# Power_circuit.net
KiCad netlist of a schematic drawn in Altium Designer
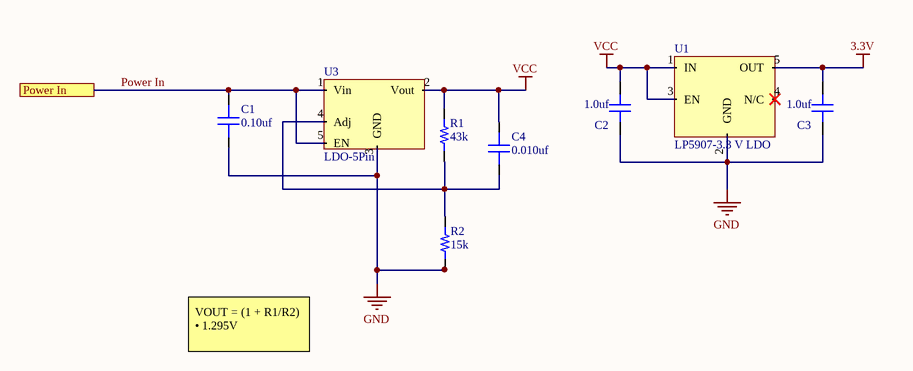
[diagram p0: Power circuit.SchDoc]

(export (version "E")
  (design (tool "Eeschema 10.0.6"))
  (components
    (comp (ref "C1")
      (value "0.10uf")
      (footprint "CAP 0603/1608")
      (fields
        (field (name "Comment") "Capacitor MLCC 0.10uf 16V CAP 0603/1608")
        (field (name "CREATED_BY") "Nick Mah")
      )
      (libsource (lib "Altium-Lib") (part "Capacitor"))
    )
    (comp (ref "C2")
      (value "1.0uf")
      (footprint "CAP 0603/1608")
      (fields
        (field (name "Comment") "Capacitor MLCC 1.0uf 16V CAP 0603/1608")
        (field (name "CREATED_BY") "Nick Mah")
      )
      (libsource (lib "") (part "Capacitor_1"))
    )
    (comp (ref "C3")
      (value "1.0uf")
      (footprint "CAP 0603/1608")
      (fields
        (field (name "Comment") "Capacitor MLCC 1.0uf 16V CAP 0603/1608")
        (field (name "CREATED_BY") "Nick Mah")
      )
      (libsource (lib "") (part "Capacitor_1"))
    )
    (comp (ref "C4")
      (value "0.010uf")
      (footprint "CAP 0603/1608")
      (fields
        (field (name "Comment") "Capacitor MLCC 0.010uf 16V CAP 0603/1608")
        (field (name "CREATED_BY") "Nick Mah")
      )
      (libsource (lib "Altium-Lib") (part "Capacitor"))
    )
    (comp (ref "R1")
      (value "43k")
      (footprint "RES 0603/1608")
      (fields
        (field (name "TOLERANCE") "1%")
        (field (name "POWER") "1/10W")
        (field (name "Comment") "Resistor 43k 0603 1/10W 1%")
        (field (name "CREATED_BY") "Nick Mah")
      )
      (libsource (lib "Altium-Lib") (part "Resistor"))
    )
    (comp (ref "R2")
      (value "15k")
      (footprint "RES 0603/1608")
      (fields
        (field (name "TOLERANCE") "1%")
        (field (name "POWER") "1/10W")
        (field (name "Comment") "Resistor 15k 0603 1/10W 1%")
        (field (name "CREATED_BY") "Nick Mah")
      )
      (libsource (lib "Altium-Lib") (part "Resistor"))
    )
    (comp (ref "U1")
      (value "LP5907-3.3 V LDO")
      (footprint "SOT23-5")
      (fields (field (name "MFRPARTNO") "LP5907MFX-3.3/NOPB"))
      (libsource (lib "Altium-Lib") (part "LP5907-3.3 V LDO"))
    )
    (comp (ref "U3")
      (value "LDO-5Pin")
      (footprint "SOT223-5")
      (fields (field (name "MFRPARTNO") "REG104GA-A"))
      (libsource (lib "Altium-Lib") (part "LDO-5Pin"))
    )
  )
  (nets
    (net (code "1") (name "/Power In") (class "Default")
      (node (ref "C1") (pin "2") (pinfunction "2_2") (pintype "passive"))
      (node (ref "U3") (pin "1") (pinfunction "Vin_1") (pintype "input"))
      (node (ref "U3") (pin "5") (pinfunction "EN_5") (pintype "input"))
    )
    (net (code "2") (name "3.3V") (class "Default")
      (node (ref "C3") (pin "2") (pinfunction "2_2") (pintype "passive"))
      (node (ref "U1") (pin "5") (pinfunction "OUT_5") (pintype "input"))
    )
    (net (code "3") (name "GND") (class "Default")
      (node (ref "C1") (pin "1") (pinfunction "1_1") (pintype "passive"))
      (node (ref "C2") (pin "1") (pinfunction "1_1") (pintype "passive"))
      (node (ref "C3") (pin "1") (pinfunction "1_1") (pintype "passive"))
      (node (ref "R2") (pin "1") (pinfunction "1_1") (pintype "passive"))
      (node (ref "U1") (pin "2") (pinfunction "GND_2") (pintype "input"))
      (node (ref "U3") (pin "3") (pinfunction "GND_3") (pintype "input"))
    )
    (net (code "4") (name "Net-(U3-Adj)") (class "Default")
      (node (ref "C4") (pin "1") (pinfunction "1_1") (pintype "passive"))
      (node (ref "R1") (pin "1") (pinfunction "1_1") (pintype "passive"))
      (node (ref "R2") (pin "2") (pinfunction "2_2") (pintype "passive"))
      (node (ref "U3") (pin "4") (pinfunction "Adj_4") (pintype "input"))
    )
    (net (code "5") (name "VCC") (class "Default")
      (node (ref "C2") (pin "2") (pinfunction "2_2") (pintype "passive"))
      (node (ref "C4") (pin "2") (pinfunction "2_2") (pintype "passive"))
      (node (ref "R1") (pin "2") (pinfunction "2_2") (pintype "passive"))
      (node (ref "U1") (pin "1") (pinfunction "IN_1") (pintype "input"))
      (node (ref "U1") (pin "3") (pinfunction "EN_3") (pintype "input"))
      (node (ref "U3") (pin "2") (pinfunction "Vout_2") (pintype "input"))
    )
    (net (code "6") (name "unconnected-(U1-N{slash}C-Pad4)") (class "Default")
      (node (ref "U1") (pin "4") (pinfunction "N/C_4") (pintype "input+no_connect"))
    )
  )
)
